# ESC2.net
KiCad netlist of a schematic drawn in Altium Designer
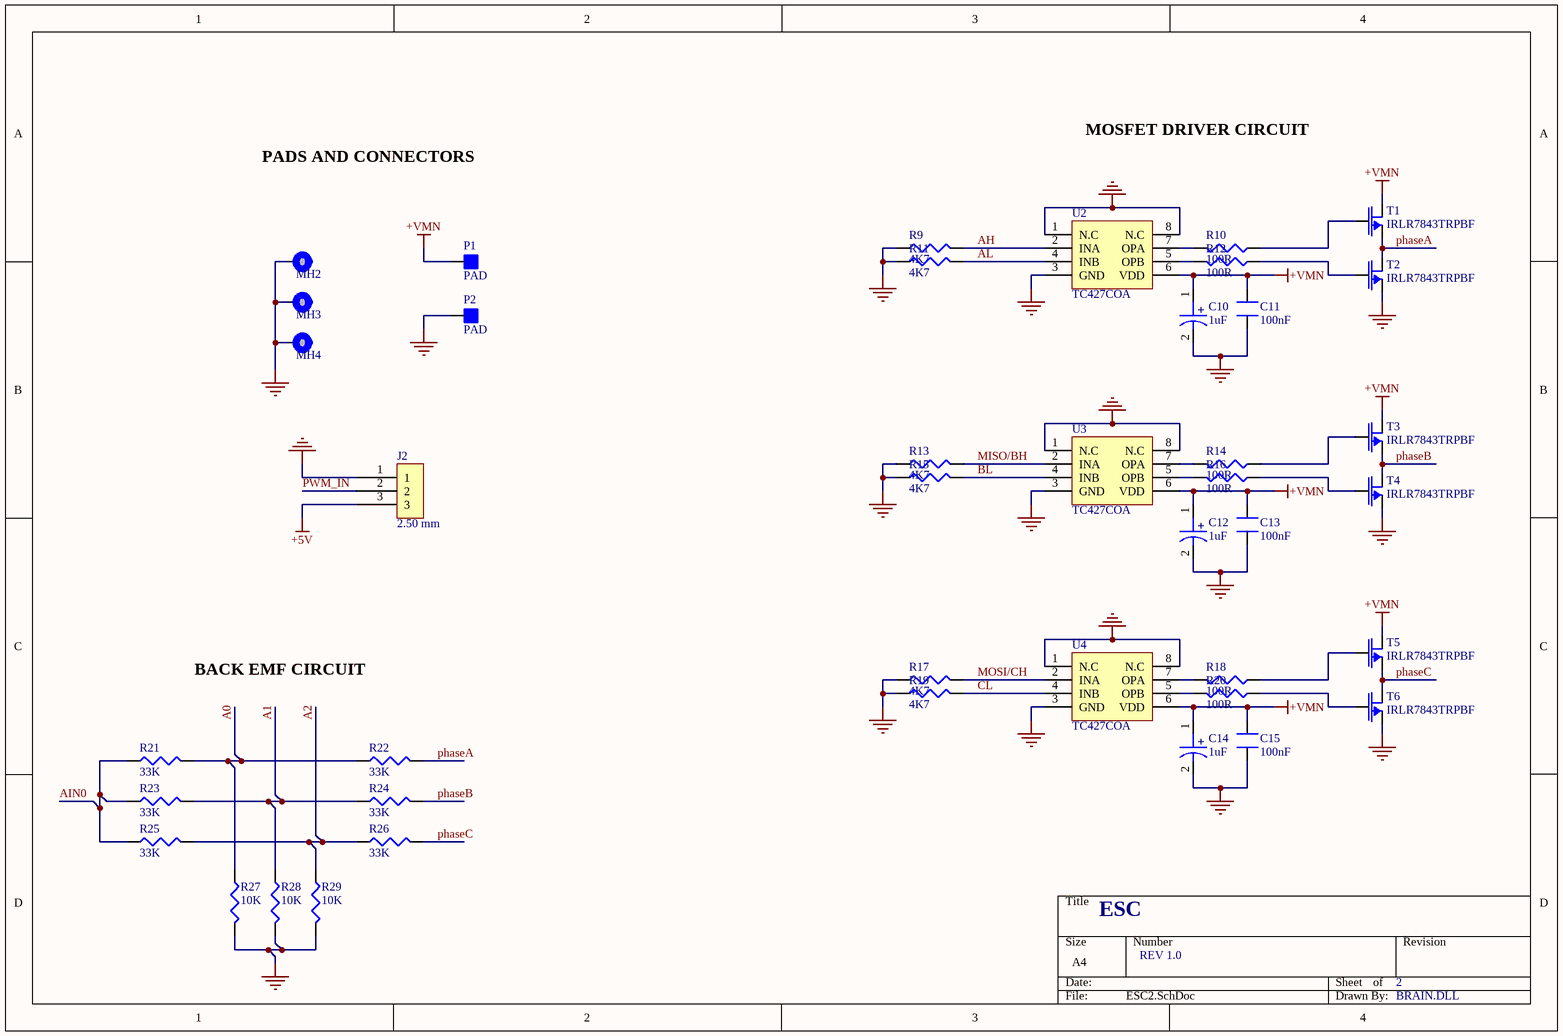
[diagram p0: ESC2.SchDoc]

(export (version "E")
  (design (tool "Eeschema 10.0.6"))
  (components
    (comp (ref "C10")
      (value "1uF")
      (footprint "1206 TANTAL CAP")
      (description "Cap Tant Solid 1uF 35V A CASE 10% (3.2 X 1.6 X 1.6mm) SMD 3216-18 7.5 Ohm 125 C T/R")
      (fields
        (field (name "MANUFACTURER") "KEMET")
        (field (name "MANUFACTURER PART NUMBER") "T491A105K035AT")
      )
      (libsource (lib "ESClib1") (part "T491A105K035AT"))
    )
    (comp (ref "C11")
      (value "100nF")
      (footprint "Z0603")
      (description "Multi Layer Ceramic Capacitor (MLCC) / Cap Ceramic 0.1uF 50V X7R 10% Pad SMD 0603 125°C T/R")
      (fields
        (field (name "MANUFACTURER") "Samsung")
        (field (name "MANUFACTURER PART NUMBER") "CL10B104KB8NNNC")
      )
      (libsource (lib "ESClib1") (part "CL10B104KB8NNNC"))
    )
    (comp (ref "C12")
      (value "1uF")
      (footprint "1206 TANTAL CAP")
      (description "Cap Tant Solid 1uF 35V A CASE 10% (3.2 X 1.6 X 1.6mm) SMD 3216-18 7.5 Ohm 125 C T/R")
      (fields
        (field (name "MANUFACTURER") "KEMET")
        (field (name "MANUFACTURER PART NUMBER") "T491A105K035AT")
      )
      (libsource (lib "ESClib1") (part "T491A105K035AT"))
    )
    (comp (ref "C13")
      (value "100nF")
      (footprint "Z0603")
      (description "Multi Layer Ceramic Capacitor (MLCC) / Cap Ceramic 0.1uF 50V X7R 10% Pad SMD 0603 125°C T/R")
      (fields
        (field (name "MANUFACTURER") "Samsung")
        (field (name "MANUFACTURER PART NUMBER") "CL10B104KB8NNNC")
      )
      (libsource (lib "ESClib1") (part "CL10B104KB8NNNC"))
    )
    (comp (ref "C14")
      (value "1uF")
      (footprint "1206 TANTAL CAP")
      (description "Cap Tant Solid 1uF 35V A CASE 10% (3.2 X 1.6 X 1.6mm) SMD 3216-18 7.5 Ohm 125 C T/R")
      (fields
        (field (name "MANUFACTURER") "KEMET")
        (field (name "MANUFACTURER PART NUMBER") "T491A105K035AT")
      )
      (libsource (lib "ESClib1") (part "T491A105K035AT"))
    )
    (comp (ref "C15")
      (value "100nF")
      (footprint "Z0603")
      (description "Multi Layer Ceramic Capacitor (MLCC) / Cap Ceramic 0.1uF 50V X7R 10% Pad SMD 0603 125°C T/R")
      (fields
        (field (name "MANUFACTURER") "Samsung")
        (field (name "MANUFACTURER PART NUMBER") "CL10B104KB8NNNC")
      )
      (libsource (lib "ESClib1") (part "CL10B104KB8NNNC"))
    )
    (comp (ref "J2")
      (value "2.50 mm")
      (footprint "L-KLS1-XL4-2.50-03-R")
      (libsource (lib "ESClib1") (part "L-KLS1-XL4-2.50-03-R"))
    )
    (comp (ref "MH2")
      (value "MH_7.4MMC_3.2MMD")
      (footprint "MH_7.4MMC_3.2MMD_NON_COPPER_NPLT")
      (description "Mounting Hole 7.4 mm Diameter (Non Copper), 3.2 mm Drill NPTH")
      (libsource (lib "ESClib1") (part "MH_7.4MMNC_3.2MMD"))
    )
    (comp (ref "MH3")
      (value "MH_7.4MMC_3.2MMD")
      (footprint "MH_7.4MMC_3.2MMD_NON_COPPER_NPLT")
      (description "Mounting Hole 7.4 mm Diameter (Non Copper), 3.2 mm Drill NPTH")
      (libsource (lib "ESClib1") (part "MH_7.4MMNC_3.2MMD"))
    )
    (comp (ref "MH4")
      (value "MH_7.4MMC_3.2MMD")
      (footprint "MH_7.4MMC_3.2MMD_NON_COPPER_NPLT")
      (description "Mounting Hole 7.4 mm Diameter (Non Copper), 3.2 mm Drill NPTH")
      (libsource (lib "ESClib1") (part "MH_7.4MMNC_3.2MMD"))
    )
    (comp (ref "P1") (value "PAD") (footprint "SQARE_PAD") (libsource (lib "ESClib1") (part "SQARE_PAD")))
    (comp (ref "P2") (value "PAD") (footprint "SQARE_PAD") (libsource (lib "ESClib1") (part "SQARE_PAD")))
    (comp (ref "R9")
      (value "4K7")
      (footprint "Z0603")
      (fields
        (field (name "MANUFACTURER") "Multicomp")
        (field (name "MANUFACTURER PART NUMBER") "MC0603SAF4701T5E")
        (field (name "TOLERANCE") "1%")
      )
      (libsource (lib "ESClib1") (part "MC0603SAF4701T5E"))
    )
    (comp (ref "R10") (value "100R") (footprint "Z0603") (libsource (lib "ESClib1") (part "0603SAJ0101T5E")))
    (comp (ref "R11")
      (value "4K7")
      (footprint "Z0603")
      (fields
        (field (name "MANUFACTURER") "Multicomp")
        (field (name "MANUFACTURER PART NUMBER") "MC0603SAF4701T5E")
        (field (name "TOLERANCE") "1%")
      )
      (libsource (lib "ESClib1") (part "MC0603SAF4701T5E"))
    )
    (comp (ref "R12") (value "100R") (footprint "Z0603") (libsource (lib "ESClib1") (part "0603SAJ0101T5E")))
    (comp (ref "R13")
      (value "4K7")
      (footprint "Z0603")
      (fields
        (field (name "MANUFACTURER") "Multicomp")
        (field (name "MANUFACTURER PART NUMBER") "MC0603SAF4701T5E")
        (field (name "TOLERANCE") "1%")
      )
      (libsource (lib "ESClib1") (part "MC0603SAF4701T5E"))
    )
    (comp (ref "R14") (value "100R") (footprint "Z0603") (libsource (lib "ESClib1") (part "0603SAJ0101T5E")))
    (comp (ref "R15")
      (value "4K7")
      (footprint "Z0603")
      (fields
        (field (name "MANUFACTURER") "Multicomp")
        (field (name "MANUFACTURER PART NUMBER") "MC0603SAF4701T5E")
        (field (name "TOLERANCE") "1%")
      )
      (libsource (lib "ESClib1") (part "MC0603SAF4701T5E"))
    )
    (comp (ref "R16") (value "100R") (footprint "Z0603") (libsource (lib "ESClib1") (part "0603SAJ0101T5E")))
    (comp (ref "R17")
      (value "4K7")
      (footprint "Z0603")
      (fields
        (field (name "MANUFACTURER") "Multicomp")
        (field (name "MANUFACTURER PART NUMBER") "MC0603SAF4701T5E")
        (field (name "TOLERANCE") "1%")
      )
      (libsource (lib "ESClib1") (part "MC0603SAF4701T5E"))
    )
    (comp (ref "R18") (value "100R") (footprint "Z0603") (libsource (lib "ESClib1") (part "0603SAJ0101T5E")))
    (comp (ref "R19")
      (value "4K7")
      (footprint "Z0603")
      (fields
        (field (name "MANUFACTURER") "Multicomp")
        (field (name "MANUFACTURER PART NUMBER") "MC0603SAF4701T5E")
        (field (name "TOLERANCE") "1%")
      )
      (libsource (lib "ESClib1") (part "MC0603SAF4701T5E"))
    )
    (comp (ref "R20") (value "100R") (footprint "Z0603") (libsource (lib "ESClib1") (part "0603SAJ0101T5E")))
    (comp (ref "R21") (value "33K") (footprint "Z0603") (libsource (lib "ESClib1") (part "RI0603L3302FT")))
    (comp (ref "R22") (value "33K") (footprint "Z0603") (libsource (lib "ESClib1") (part "RI0603L3302FT")))
    (comp (ref "R23") (value "33K") (footprint "Z0603") (libsource (lib "ESClib1") (part "RI0603L3302FT")))
    (comp (ref "R24") (value "33K") (footprint "Z0603") (libsource (lib "ESClib1") (part "RI0603L3302FT")))
    (comp (ref "R25") (value "33K") (footprint "Z0603") (libsource (lib "ESClib1") (part "RI0603L3302FT")))
    (comp (ref "R26") (value "33K") (footprint "Z0603") (libsource (lib "ESClib1") (part "RI0603L3302FT")))
    (comp (ref "R27") (value "10K") (footprint "Z0603") (libsource (lib "ESClib1") (part "CQ03SAF1002T5E")))
    (comp (ref "R28") (value "10K") (footprint "Z0603") (libsource (lib "ESClib1") (part "CQ03SAF1002T5E")))
    (comp (ref "R29") (value "10K") (footprint "Z0603") (libsource (lib "ESClib1") (part "CQ03SAF1002T5E")))
    (comp (ref "T1")
      (value "IRLR7843TRPBF")
      (footprint "TO-252-3")
      (description "MOSFET, 30V, 161A, 3.3 mOhm, 34 nC Qg, Logic Level, D-Pak")
      (fields (field (name "MANUFACTURER") "International Rectifier"))
      (libsource (lib "ESClib1") (part "IRLR7843TRPBF"))
    )
    (comp (ref "T2")
      (value "IRLR7843TRPBF")
      (footprint "TO-252-3")
      (description "MOSFET, 30V, 161A, 3.3 mOhm, 34 nC Qg, Logic Level, D-Pak")
      (fields (field (name "MANUFACTURER") "International Rectifier"))
      (libsource (lib "ESClib1") (part "IRLR7843TRPBF"))
    )
    (comp (ref "T3")
      (value "IRLR7843TRPBF")
      (footprint "TO-252-3")
      (description "MOSFET, 30V, 161A, 3.3 mOhm, 34 nC Qg, Logic Level, D-Pak")
      (fields (field (name "MANUFACTURER") "International Rectifier"))
      (libsource (lib "ESClib1") (part "IRLR7843TRPBF"))
    )
    (comp (ref "T4")
      (value "IRLR7843TRPBF")
      (footprint "TO-252-3")
      (description "MOSFET, 30V, 161A, 3.3 mOhm, 34 nC Qg, Logic Level, D-Pak")
      (fields (field (name "MANUFACTURER") "International Rectifier"))
      (libsource (lib "ESClib1") (part "IRLR7843TRPBF"))
    )
    (comp (ref "T5")
      (value "IRLR7843TRPBF")
      (footprint "TO-252-3")
      (description "MOSFET, 30V, 161A, 3.3 mOhm, 34 nC Qg, Logic Level, D-Pak")
      (fields (field (name "MANUFACTURER") "International Rectifier"))
      (libsource (lib "ESClib1") (part "IRLR7843TRPBF"))
    )
    (comp (ref "T6")
      (value "IRLR7843TRPBF")
      (footprint "TO-252-3")
      (description "MOSFET, 30V, 161A, 3.3 mOhm, 34 nC Qg, Logic Level, D-Pak")
      (fields (field (name "MANUFACTURER") "International Rectifier"))
      (libsource (lib "ESClib1") (part "IRLR7843TRPBF"))
    )
    (comp (ref "U2")
      (value "TC427COA")
      (footprint "SOIC-8")
      (description "IC MOSFET DVR 1.5A DUAL HS 8SOIC")
      (fields (field (name "MANUFACTURER") "Microchip"))
      (libsource (lib "ESClib1") (part "TC427COA"))
    )
    (comp (ref "U3")
      (value "TC427COA")
      (footprint "SOIC-8")
      (description "IC MOSFET DVR 1.5A DUAL HS 8SOIC")
      (fields (field (name "MANUFACTURER") "Microchip"))
      (libsource (lib "ESClib1") (part "TC427COA"))
    )
    (comp (ref "U4")
      (value "TC427COA")
      (footprint "SOIC-8")
      (description "IC MOSFET DVR 1.5A DUAL HS 8SOIC")
      (fields (field (name "MANUFACTURER") "Microchip"))
      (libsource (lib "ESClib1") (part "TC427COA"))
    )
  )
  (nets
    (net (code "1") (name "+5V") (class "Default")
      (node (ref "J2") (pin "3") (pinfunction "3_3") (pintype "passive"))
    )
    (net (code "2") (name "+VMN") (class "Default")
      (node (ref "C10") (pin "1") (pinfunction "1_1") (pintype "passive"))
      (node (ref "C11") (pin "1") (pinfunction "1_1") (pintype "passive"))
      (node (ref "C12") (pin "1") (pinfunction "1_1") (pintype "passive"))
      (node (ref "C13") (pin "1") (pinfunction "1_1") (pintype "passive"))
      (node (ref "C14") (pin "1") (pinfunction "1_1") (pintype "passive"))
      (node (ref "C15") (pin "1") (pinfunction "1_1") (pintype "passive"))
      (node (ref "P1") (pin "1") (pinfunction "1_1") (pintype "passive"))
      (node (ref "T1") (pin "2") (pinfunction "DRAIN_2") (pintype "passive"))
      (node (ref "T3") (pin "2") (pinfunction "DRAIN_2") (pintype "passive"))
      (node (ref "T5") (pin "2") (pinfunction "DRAIN_2") (pintype "passive"))
      (node (ref "U2") (pin "6") (pinfunction "VDD_6") (pintype "passive"))
      (node (ref "U3") (pin "6") (pinfunction "VDD_6") (pintype "passive"))
      (node (ref "U4") (pin "6") (pinfunction "VDD_6") (pintype "passive"))
    )
    (net (code "3") (name "/A0") (class "Default")
      (node (ref "R21") (pin "2") (pinfunction "2_2") (pintype "passive"))
      (node (ref "R22") (pin "1") (pinfunction "1_1") (pintype "passive"))
      (node (ref "R27") (pin "1") (pinfunction "1_1") (pintype "passive"))
    )
    (net (code "4") (name "/A1") (class "Default")
      (node (ref "R23") (pin "2") (pinfunction "2_2") (pintype "passive"))
      (node (ref "R24") (pin "1") (pinfunction "1_1") (pintype "passive"))
      (node (ref "R28") (pin "1") (pinfunction "1_1") (pintype "passive"))
    )
    (net (code "5") (name "/A2") (class "Default")
      (node (ref "R25") (pin "2") (pinfunction "2_2") (pintype "passive"))
      (node (ref "R26") (pin "1") (pinfunction "1_1") (pintype "passive"))
      (node (ref "R29") (pin "1") (pinfunction "1_1") (pintype "passive"))
    )
    (net (code "6") (name "/AH") (class "Default")
      (node (ref "R9") (pin "2") (pinfunction "2_2") (pintype "passive"))
      (node (ref "U2") (pin "2") (pinfunction "INA_2") (pintype "passive"))
    )
    (net (code "7") (name "/AIN0") (class "Default")
      (node (ref "R21") (pin "1") (pinfunction "1_1") (pintype "passive"))
      (node (ref "R23") (pin "1") (pinfunction "1_1") (pintype "passive"))
      (node (ref "R25") (pin "1") (pinfunction "1_1") (pintype "passive"))
    )
    (net (code "8") (name "/AL") (class "Default")
      (node (ref "R11") (pin "2") (pinfunction "2_2") (pintype "passive"))
      (node (ref "U2") (pin "4") (pinfunction "INB_4") (pintype "passive"))
    )
    (net (code "9") (name "/BL") (class "Default")
      (node (ref "R15") (pin "2") (pinfunction "2_2") (pintype "passive"))
      (node (ref "U3") (pin "4") (pinfunction "INB_4") (pintype "passive"))
    )
    (net (code "10") (name "/CL") (class "Default")
      (node (ref "R19") (pin "2") (pinfunction "2_2") (pintype "passive"))
      (node (ref "U4") (pin "4") (pinfunction "INB_4") (pintype "passive"))
    )
    (net (code "11") (name "/MISO{slash}BH") (class "Default")
      (node (ref "R13") (pin "2") (pinfunction "2_2") (pintype "passive"))
      (node (ref "U3") (pin "2") (pinfunction "INA_2") (pintype "passive"))
    )
    (net (code "12") (name "/MOSI{slash}CH") (class "Default")
      (node (ref "R17") (pin "2") (pinfunction "2_2") (pintype "passive"))
      (node (ref "U4") (pin "2") (pinfunction "INA_2") (pintype "passive"))
    )
    (net (code "13") (name "/PWM_IN") (class "Default")
      (node (ref "J2") (pin "2") (pinfunction "2_2") (pintype "passive"))
    )
    (net (code "14") (name "/phaseA") (class "Default")
      (node (ref "R22") (pin "2") (pinfunction "2_2") (pintype "passive"))
      (node (ref "T1") (pin "3") (pinfunction "SOURCE_3") (pintype "passive"))
      (node (ref "T2") (pin "2") (pinfunction "DRAIN_2") (pintype "passive"))
    )
    (net (code "15") (name "/phaseB") (class "Default")
      (node (ref "R24") (pin "2") (pinfunction "2_2") (pintype "passive"))
      (node (ref "T3") (pin "3") (pinfunction "SOURCE_3") (pintype "passive"))
      (node (ref "T4") (pin "2") (pinfunction "DRAIN_2") (pintype "passive"))
    )
    (net (code "16") (name "/phaseC") (class "Default")
      (node (ref "R26") (pin "2") (pinfunction "2_2") (pintype "passive"))
      (node (ref "T5") (pin "3") (pinfunction "SOURCE_3") (pintype "passive"))
      (node (ref "T6") (pin "2") (pinfunction "DRAIN_2") (pintype "passive"))
    )
    (net (code "17") (name "GND") (class "Default")
      (node (ref "C10") (pin "2") (pinfunction "2_2") (pintype "passive"))
      (node (ref "C11") (pin "2") (pinfunction "2_2") (pintype "passive"))
      (node (ref "C12") (pin "2") (pinfunction "2_2") (pintype "passive"))
      (node (ref "C13") (pin "2") (pinfunction "2_2") (pintype "passive"))
      (node (ref "C14") (pin "2") (pinfunction "2_2") (pintype "passive"))
      (node (ref "C15") (pin "2") (pinfunction "2_2") (pintype "passive"))
      (node (ref "J2") (pin "1") (pinfunction "1_1") (pintype "passive"))
      (node (ref "MH2") (pin "1") (pinfunction "1_1") (pintype "passive"))
      (node (ref "MH3") (pin "1") (pinfunction "1_1") (pintype "passive"))
      (node (ref "MH4") (pin "1") (pinfunction "1_1") (pintype "passive"))
      (node (ref "P2") (pin "1") (pinfunction "1_1") (pintype "passive"))
      (node (ref "R11") (pin "1") (pinfunction "1_1") (pintype "passive"))
      (node (ref "R13") (pin "1") (pinfunction "1_1") (pintype "passive"))
      (node (ref "R15") (pin "1") (pinfunction "1_1") (pintype "passive"))
      (node (ref "R17") (pin "1") (pinfunction "1_1") (pintype "passive"))
      (node (ref "R19") (pin "1") (pinfunction "1_1") (pintype "passive"))
      (node (ref "R27") (pin "2") (pinfunction "2_2") (pintype "passive"))
      (node (ref "R28") (pin "2") (pinfunction "2_2") (pintype "passive"))
      (node (ref "R29") (pin "2") (pinfunction "2_2") (pintype "passive"))
      (node (ref "R9") (pin "1") (pinfunction "1_1") (pintype "passive"))
      (node (ref "T2") (pin "3") (pinfunction "SOURCE_3") (pintype "passive"))
      (node (ref "T4") (pin "3") (pinfunction "SOURCE_3") (pintype "passive"))
      (node (ref "T6") (pin "3") (pinfunction "SOURCE_3") (pintype "passive"))
      (node (ref "U2") (pin "1") (pinfunction "N.C_1") (pintype "passive"))
      (node (ref "U2") (pin "3") (pinfunction "GND_3") (pintype "passive"))
      (node (ref "U2") (pin "8") (pinfunction "N.C_8") (pintype "passive"))
      (node (ref "U3") (pin "1") (pinfunction "N.C_1") (pintype "passive"))
      (node (ref "U3") (pin "3") (pinfunction "GND_3") (pintype "passive"))
      (node (ref "U3") (pin "8") (pinfunction "N.C_8") (pintype "passive"))
      (node (ref "U4") (pin "1") (pinfunction "N.C_1") (pintype "passive"))
      (node (ref "U4") (pin "3") (pinfunction "GND_3") (pintype "passive"))
      (node (ref "U4") (pin "8") (pinfunction "N.C_8") (pintype "passive"))
    )
    (net (code "18") (name "Net-(T1-GATE)") (class "Default")
      (node (ref "R10") (pin "1") (pinfunction "1_1") (pintype "passive"))
      (node (ref "T1") (pin "1") (pinfunction "GATE_1") (pintype "passive"))
    )
    (net (code "19") (name "Net-(T2-GATE)") (class "Default")
      (node (ref "R12") (pin "1") (pinfunction "1_1") (pintype "passive"))
      (node (ref "T2") (pin "1") (pinfunction "GATE_1") (pintype "passive"))
    )
    (net (code "20") (name "Net-(T3-GATE)") (class "Default")
      (node (ref "R14") (pin "1") (pinfunction "1_1") (pintype "passive"))
      (node (ref "T3") (pin "1") (pinfunction "GATE_1") (pintype "passive"))
    )
    (net (code "21") (name "Net-(T4-GATE)") (class "Default")
      (node (ref "R16") (pin "1") (pinfunction "1_1") (pintype "passive"))
      (node (ref "T4") (pin "1") (pinfunction "GATE_1") (pintype "passive"))
    )
    (net (code "22") (name "Net-(T5-GATE)") (class "Default")
      (node (ref "R18") (pin "1") (pinfunction "1_1") (pintype "passive"))
      (node (ref "T5") (pin "1") (pinfunction "GATE_1") (pintype "passive"))
    )
    (net (code "23") (name "Net-(T6-GATE)") (class "Default")
      (node (ref "R20") (pin "1") (pinfunction "1_1") (pintype "passive"))
      (node (ref "T6") (pin "1") (pinfunction "GATE_1") (pintype "passive"))
    )
    (net (code "24") (name "Net-(U2-OPA)") (class "Default")
      (node (ref "R10") (pin "2") (pinfunction "2_2") (pintype "passive"))
      (node (ref "U2") (pin "7") (pinfunction "OPA_7") (pintype "passive"))
    )
    (net (code "25") (name "Net-(U2-OPB)") (class "Default")
      (node (ref "R12") (pin "2") (pinfunction "2_2") (pintype "passive"))
      (node (ref "U2") (pin "5") (pinfunction "OPB_5") (pintype "passive"))
    )
    (net (code "26") (name "Net-(U3-OPA)") (class "Default")
      (node (ref "R14") (pin "2") (pinfunction "2_2") (pintype "passive"))
      (node (ref "U3") (pin "7") (pinfunction "OPA_7") (pintype "passive"))
    )
    (net (code "27") (name "Net-(U3-OPB)") (class "Default")
      (node (ref "R16") (pin "2") (pinfunction "2_2") (pintype "passive"))
      (node (ref "U3") (pin "5") (pinfunction "OPB_5") (pintype "passive"))
    )
    (net (code "28") (name "Net-(U4-OPA)") (class "Default")
      (node (ref "R18") (pin "2") (pinfunction "2_2") (pintype "passive"))
      (node (ref "U4") (pin "7") (pinfunction "OPA_7") (pintype "passive"))
    )
    (net (code "29") (name "Net-(U4-OPB)") (class "Default")
      (node (ref "R20") (pin "2") (pinfunction "2_2") (pintype "passive"))
      (node (ref "U4") (pin "5") (pinfunction "OPB_5") (pintype "passive"))
    )
  )
)
